# SCH_Uhhhhhhh_2025-04-25.net
KiCad netlist of a schematic drawn in EasyEDA
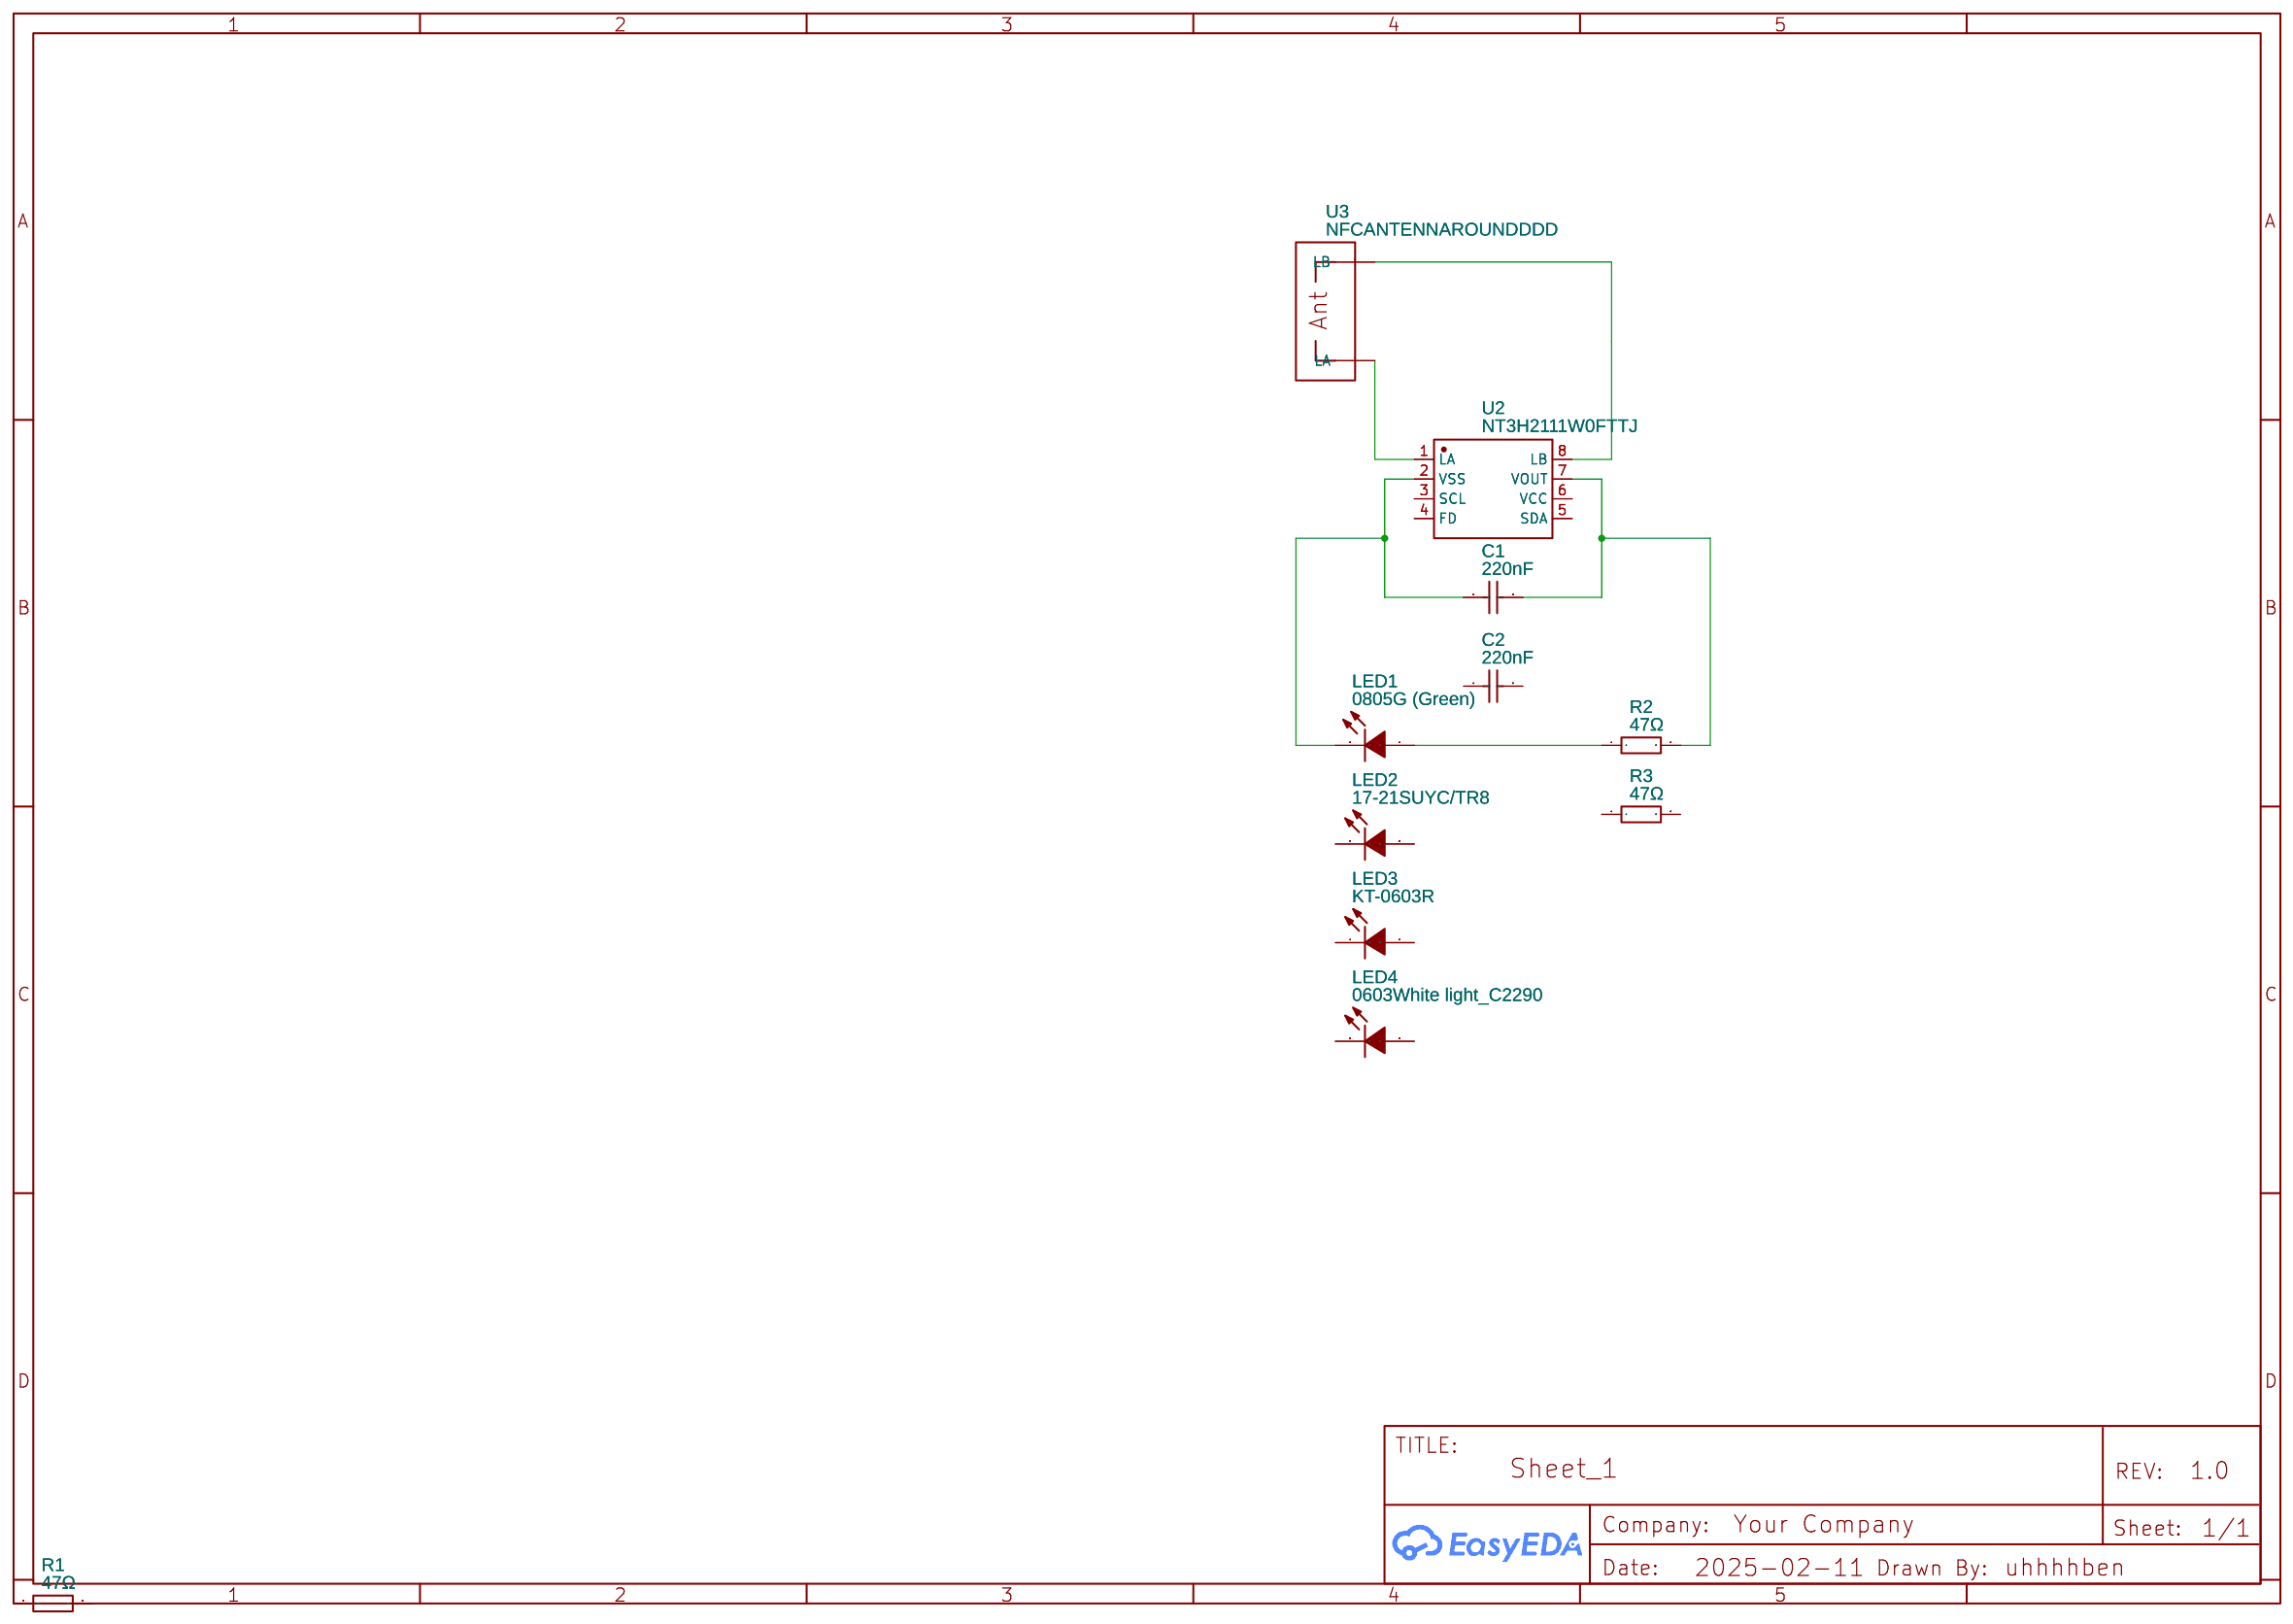
[diagram p0: schematic sheet]

(export (version "E")
  (design (tool "Eeschema 10.0.6"))
  (components
    (comp (ref "C1")
      (value "220nF")
      (fields
        (field (name "Manufacturer Part") "CL05B224KO5NNNC")
        (field (name "Manufacturer") "SAMSUNG(三星)")
      )
      (libsource (lib "") (part "CL05B224KO5NNNC"))
    )
    (comp (ref "C2")
      (value "220nF")
      (fields
        (field (name "Manufacturer Part") "CL05B224KO5NNNC")
        (field (name "Manufacturer") "SAMSUNG(三星)")
      )
      (libsource (lib "") (part "CL05B224KO5NNNC"))
    )
    (comp (ref "LED1")
      (value "0805G (Green)")
      (fields (field (name "Manufacturer Part") "KT-0805G") (field (name "Manufacturer") "KENTO"))
      (libsource (lib "") (part "0805G (Green)"))
    )
    (comp (ref "LED2")
      (value "17-21SUYC/TR8")
      (fields (field (name "Manufacturer Part") "KT-0805黄灯") (field (name "Manufacturer") "KENTO"))
      (libsource (lib "") (part "17-21SUYC/TR8"))
    )
    (comp (ref "LED3")
      (value "KT-0603R")
      (fields (field (name "Manufacturer") "KENTO"))
      (libsource (lib "") (part "KT-0603R"))
    )
    (comp (ref "LED4")
      (value "0603White light_C2290")
      (fields (field (name "Manufacturer Part") "KT-0603W") (field (name "Manufacturer") "KENTO"))
      (libsource (lib "") (part "0603White light_C2290"))
    )
    (comp (ref "R1")
      (value "47Ω")
      (fields
        (field (name "Manufacturer Part") "0603WAF470JT5E")
        (field (name "Manufacturer") "UNI-ROYAL(厚声)")
      )
      (libsource (lib "") (part "0603WAF470JT5E"))
    )
    (comp (ref "R2")
      (value "47Ω")
      (fields
        (field (name "Manufacturer Part") "0603WAF470JT5E")
        (field (name "Manufacturer") "UNI-ROYAL(厚声)")
      )
      (libsource (lib "") (part "0603WAF470JT5E"))
    )
    (comp (ref "R3")
      (value "47Ω")
      (fields
        (field (name "Manufacturer Part") "0603WAF470JT5E")
        (field (name "Manufacturer") "UNI-ROYAL(厚声)")
      )
      (libsource (lib "") (part "0603WAF470JT5E"))
    )
    (comp (ref "U2")
      (value "NT3H2111W0FTTJ")
      (fields (field (name "Manufacturer") "NXP(恩智浦)"))
      (libsource (lib "") (part "NT3H2111W0FTTJ"))
    )
    (comp (ref "U3") (value "NFCANTENNAROUNDDDD") (libsource (lib "") (part "NFCANTENNAROUNDDDD")))
  )
  (nets
    (net (code "1") (name "Net-(LED1-A)") (class "Default")
      (node (ref "LED1") (pin "1") (pinfunction "A_1") (pintype "unspecified"))
      (node (ref "R2") (pin "1") (pinfunction "1_1") (pintype "input"))
    )
    (net (code "2") (name "Net-(LED1-K)") (class "Default")
      (node (ref "C1") (pin "1") (pinfunction "1_1") (pintype "input"))
      (node (ref "LED1") (pin "2") (pinfunction "K_2") (pintype "unspecified"))
      (node (ref "U2") (pin "2") (pinfunction "VSS_2") (pintype "unspecified"))
    )
    (net (code "3") (name "Net-(U2-LA)") (class "Default")
      (node (ref "U2") (pin "1") (pinfunction "LA_1") (pintype "unspecified"))
      (node (ref "U3") (pin "LA") (pinfunction "LA_LA") (pintype "unspecified"))
    )
    (net (code "4") (name "Net-(U2-LB)") (class "Default")
      (node (ref "U2") (pin "8") (pinfunction "LB_8") (pintype "unspecified"))
      (node (ref "U3") (pin "LB") (pinfunction "LB_LB") (pintype "unspecified"))
    )
    (net (code "5") (name "Net-(U2-VOUT)") (class "Default")
      (node (ref "C1") (pin "2") (pinfunction "2_2") (pintype "input"))
      (node (ref "R2") (pin "2") (pinfunction "2_2") (pintype "input"))
      (node (ref "U2") (pin "7") (pinfunction "VOUT_7") (pintype "unspecified"))
    )
    (net (code "6") (name "unconnected-(C2-Pad1)") (class "Default")
      (node (ref "C2") (pin "1") (pinfunction "1_1") (pintype "input"))
    )
    (net (code "7") (name "unconnected-(C2-Pad2)") (class "Default")
      (node (ref "C2") (pin "2") (pinfunction "2_2") (pintype "input"))
    )
    (net (code "8") (name "unconnected-(LED2-+-Pad1)") (class "Default")
      (node (ref "LED2") (pin "1") (pinfunction "+_1") (pintype "unspecified"))
    )
    (net (code "9") (name "unconnected-(LED2---Pad2)") (class "Default")
      (node (ref "LED2") (pin "2") (pinfunction "-_2") (pintype "unspecified"))
    )
    (net (code "10") (name "unconnected-(LED3-A-Pad2)") (class "Default")
      (node (ref "LED3") (pin "2") (pinfunction "A_2") (pintype "unspecified"))
    )
    (net (code "11") (name "unconnected-(LED3-K-Pad1)") (class "Default")
      (node (ref "LED3") (pin "1") (pinfunction "K_1") (pintype "unspecified"))
    )
    (net (code "12") (name "unconnected-(LED4-A-Pad1)") (class "Default")
      (node (ref "LED4") (pin "1") (pinfunction "A_1") (pintype "unspecified"))
    )
    (net (code "13") (name "unconnected-(LED4-K-Pad2)") (class "Default")
      (node (ref "LED4") (pin "2") (pinfunction "K_2") (pintype "unspecified"))
    )
    (net (code "14") (name "unconnected-(R1-Pad1)") (class "Default")
      (node (ref "R1") (pin "1") (pinfunction "1_1") (pintype "input"))
    )
    (net (code "15") (name "unconnected-(R1-Pad2)") (class "Default")
      (node (ref "R1") (pin "2") (pinfunction "2_2") (pintype "input"))
    )
    (net (code "16") (name "unconnected-(R3-Pad1)") (class "Default")
      (node (ref "R3") (pin "1") (pinfunction "1_1") (pintype "input"))
    )
    (net (code "17") (name "unconnected-(R3-Pad2)") (class "Default")
      (node (ref "R3") (pin "2") (pinfunction "2_2") (pintype "input"))
    )
    (net (code "18") (name "unconnected-(U2-FD-Pad4)") (class "Default")
      (node (ref "U2") (pin "4") (pinfunction "FD_4") (pintype "unspecified"))
    )
    (net (code "19") (name "unconnected-(U2-SCL-Pad3)") (class "Default")
      (node (ref "U2") (pin "3") (pinfunction "SCL_3") (pintype "unspecified"))
    )
    (net (code "20") (name "unconnected-(U2-SDA-Pad5)") (class "Default")
      (node (ref "U2") (pin "5") (pinfunction "SDA_5") (pintype "unspecified"))
    )
    (net (code "21") (name "unconnected-(U2-VCC-Pad6)") (class "Default")
      (node (ref "U2") (pin "6") (pinfunction "VCC_6") (pintype "unspecified"))
    )
  )
)
